# ESP8266.net
KiCad netlist of a schematic drawn in EAGLE
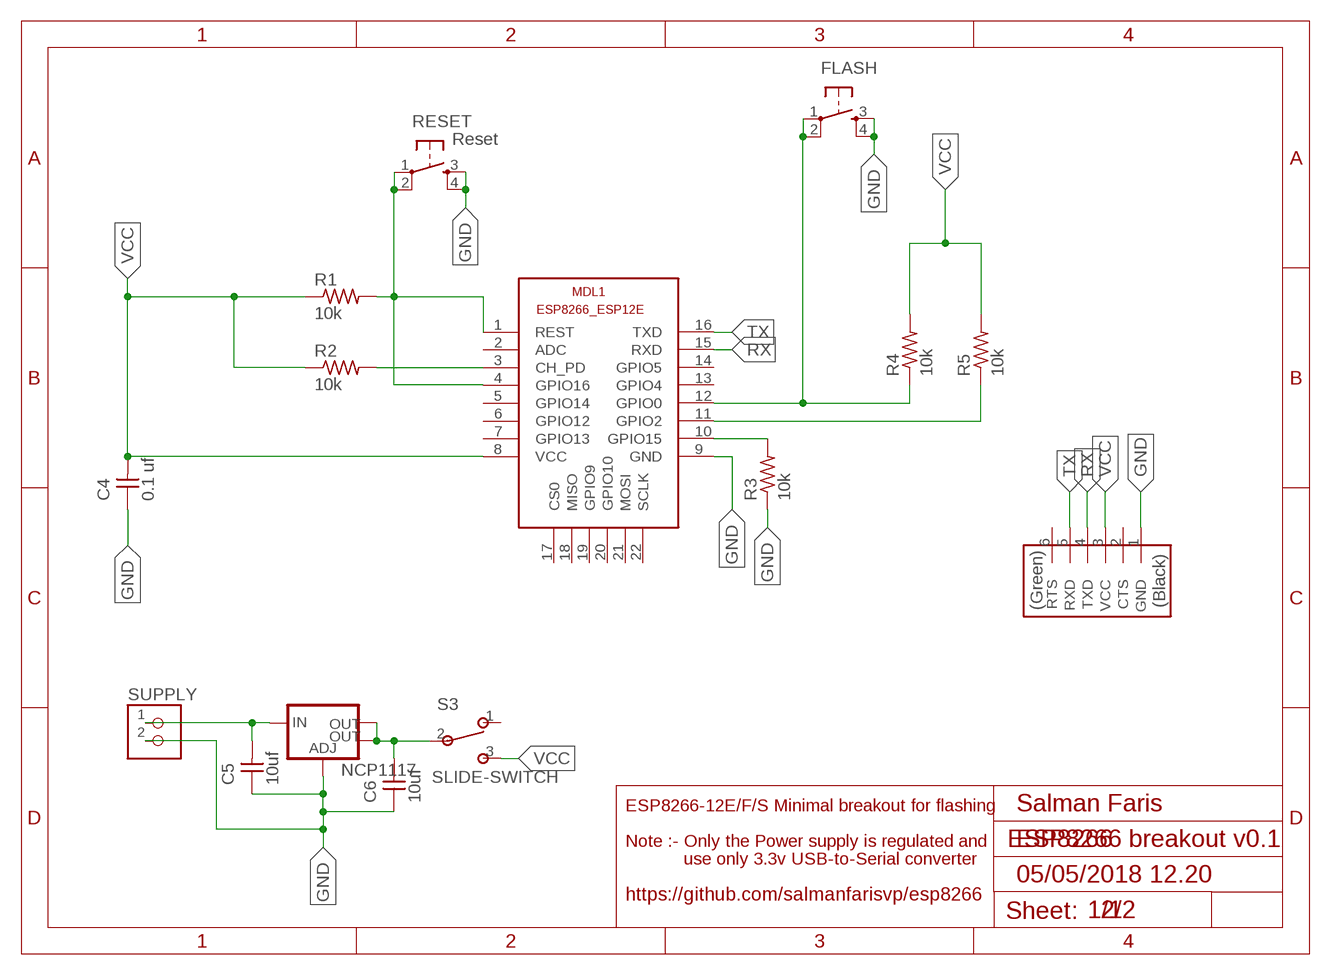
[diagram p0: schematic, sheet 2]

(export (version "E")
  (design (tool "Eeschema 10.0.6"))
  (components
    (comp (ref "C4")
      (value "0.1 uf")
      (footprint "eagle-import:C1206FAB")
      (libsource (lib "eagle-import") (part "CAP-UNPOLARIZEDFAB"))
    )
    (comp (ref "C5")
      (value "10uf")
      (footprint "eagle-import:C1206FAB")
      (libsource (lib "eagle-import") (part "CAP-UNPOLARIZEDFAB"))
    )
    (comp (ref "C6")
      (value "10uf")
      (footprint "eagle-import:C1206FAB")
      (libsource (lib "eagle-import") (part "CAP-UNPOLARIZEDFAB"))
    )
    (comp (ref "FLASH")
      (value "6MM_SWITCH6MM_SWITCH")
      (footprint "eagle-import:6MM_SWITCH")
      (libsource (lib "eagle-import") (part "6MM_SWITCH6MM_SWITCH"))
    )
    (comp (ref "FTDI")
      (value "FTDI-SMD-HEADER")
      (footprint "eagle-import:1X06SMD")
      (libsource (lib "eagle-import") (part "FTDI-SMD-HEADER"))
    )
    (comp (ref "MDL1")
      (value "ESP8266-12EESP8266-ESP12E")
      (footprint "eagle-import:ESP8266-ESP12E")
      (libsource (lib "eagle-import") (part "ESP8266-12EESP8266-ESP12E"))
    )
    (comp (ref "NCP1117")
      (value "V_REG_LM1117SOT223")
      (footprint "eagle-import:SOT223")
      (libsource (lib "eagle-import") (part "V_REG_LM1117SOT223"))
    )
    (comp (ref "R1")
      (value "10k")
      (footprint "eagle-import:R1206FAB")
      (libsource (lib "eagle-import") (part "RES-US1206FAB"))
    )
    (comp (ref "R2")
      (value "10k")
      (footprint "eagle-import:R1206FAB")
      (libsource (lib "eagle-import") (part "RES-US1206FAB"))
    )
    (comp (ref "R3")
      (value "10k")
      (footprint "eagle-import:R1206FAB")
      (libsource (lib "eagle-import") (part "RES-US1206FAB"))
    )
    (comp (ref "R4")
      (value "10k")
      (footprint "eagle-import:R1206FAB")
      (libsource (lib "eagle-import") (part "RES-US1206FAB"))
    )
    (comp (ref "R5")
      (value "10k")
      (footprint "eagle-import:R1206FAB")
      (libsource (lib "eagle-import") (part "RES-US1206FAB"))
    )
    (comp (ref "RESET")
      (value "Reset")
      (footprint "eagle-import:6MM_SWITCH")
      (libsource (lib "eagle-import") (part "6MM_SWITCH6MM_SWITCH"))
    )
    (comp (ref "S3")
      (value "SLIDE-SWITCH")
      (footprint "eagle-import:AYZ0102AGRLC")
      (libsource (lib "eagle-import") (part "SLIDE-SWITCH"))
    )
    (comp (ref "SUPPLY")
      (value "TERM-1X02-FABLAB")
      (footprint "eagle-import:ED555DS-2DS")
      (libsource (lib "eagle-import") (part "TERM-1X02-FABLAB"))
    )
  )
  (nets
    (net (code "1") (name "GND") (class "Default")
      (node (ref "C4") (pin "1") (pinfunction "1_1") (pintype "passive"))
      (node (ref "C5") (pin "1") (pinfunction "1_1") (pintype "passive"))
      (node (ref "C6") (pin "1") (pinfunction "1_1") (pintype "passive"))
      (node (ref "FLASH") (pin "3") (pinfunction "S_3") (pintype "passive"))
      (node (ref "FLASH") (pin "4") (pinfunction "S1_4") (pintype "passive"))
      (node (ref "FTDI") (pin "1") (pinfunction "GND_1") (pintype "bidirectional"))
      (node (ref "MDL1") (pin "9") (pinfunction "GND_9") (pintype "bidirectional"))
      (node (ref "NCP1117") (pin "1") (pinfunction "ADJ_1") (pintype "input"))
      (node (ref "R3") (pin "1") (pinfunction "1_1") (pintype "passive"))
      (node (ref "RESET") (pin "3") (pinfunction "S_3") (pintype "passive"))
      (node (ref "RESET") (pin "4") (pinfunction "S1_4") (pintype "passive"))
      (node (ref "SUPPLY") (pin "2") (pinfunction "2_2") (pintype "passive"))
    )
    (net (code "2") (name "Net-(C6-Pad2)") (class "Default")
      (node (ref "C6") (pin "2") (pinfunction "2_2") (pintype "passive"))
      (node (ref "NCP1117") (pin "2") (pinfunction "OUT_2") (pintype "output"))
      (node (ref "NCP1117") (pin "4") (pinfunction "OUT_4") (pintype "output"))
      (node (ref "S3") (pin "2") (pinfunction "2_2") (pintype "bidirectional"))
    )
    (net (code "3") (name "Net-(FLASH-P)") (class "Default")
      (node (ref "FLASH") (pin "1") (pinfunction "P_1") (pintype "passive"))
      (node (ref "FLASH") (pin "2") (pinfunction "P1_2") (pintype "passive"))
      (node (ref "MDL1") (pin "12") (pinfunction "GPIO0_12") (pintype "bidirectional"))
      (node (ref "R4") (pin "1") (pinfunction "1_1") (pintype "passive"))
    )
    (net (code "4") (name "Net-(MDL1-CH_PD)") (class "Default")
      (node (ref "MDL1") (pin "3") (pinfunction "CH_PD_3") (pintype "bidirectional"))
      (node (ref "R2") (pin "2") (pinfunction "2_2") (pintype "passive"))
    )
    (net (code "5") (name "Net-(MDL1-GPIO2)") (class "Default")
      (node (ref "MDL1") (pin "11") (pinfunction "GPIO2_11") (pintype "bidirectional"))
      (node (ref "R5") (pin "1") (pinfunction "1_1") (pintype "passive"))
    )
    (net (code "6") (name "Net-(MDL1-GPIO15)") (class "Default")
      (node (ref "MDL1") (pin "10") (pinfunction "GPIO15_10") (pintype "bidirectional"))
      (node (ref "R3") (pin "2") (pinfunction "2_2") (pintype "passive"))
    )
    (net (code "7") (name "Net-(MDL1-GPIO16)") (class "Default")
      (node (ref "MDL1") (pin "1") (pinfunction "REST_1") (pintype "bidirectional"))
      (node (ref "MDL1") (pin "4") (pinfunction "GPIO16_4") (pintype "bidirectional"))
      (node (ref "R1") (pin "2") (pinfunction "2_2") (pintype "passive"))
      (node (ref "RESET") (pin "1") (pinfunction "P_1") (pintype "passive"))
      (node (ref "RESET") (pin "2") (pinfunction "P1_2") (pintype "passive"))
    )
    (net (code "8") (name "Net-(NCP1117-IN)") (class "Default")
      (node (ref "C5") (pin "2") (pinfunction "2_2") (pintype "passive"))
      (node (ref "NCP1117") (pin "3") (pinfunction "IN_3") (pintype "input"))
      (node (ref "SUPPLY") (pin "1") (pinfunction "1_1") (pintype "passive"))
    )
    (net (code "9") (name "RX") (class "Default")
      (node (ref "FTDI") (pin "4") (pinfunction "TXD_4") (pintype "bidirectional"))
      (node (ref "MDL1") (pin "15") (pinfunction "RXD_15") (pintype "bidirectional"))
    )
    (net (code "10") (name "TX") (class "Default")
      (node (ref "FTDI") (pin "5") (pinfunction "RXD_5") (pintype "bidirectional"))
      (node (ref "MDL1") (pin "16") (pinfunction "TXD_16") (pintype "bidirectional"))
    )
    (net (code "11") (name "VCC") (class "Default")
      (node (ref "C4") (pin "2") (pinfunction "2_2") (pintype "passive"))
      (node (ref "FTDI") (pin "3") (pinfunction "VCC_3") (pintype "bidirectional"))
      (node (ref "MDL1") (pin "8") (pinfunction "VCC_8") (pintype "bidirectional"))
      (node (ref "R1") (pin "1") (pinfunction "1_1") (pintype "passive"))
      (node (ref "R2") (pin "1") (pinfunction "1_1") (pintype "passive"))
      (node (ref "R4") (pin "2") (pinfunction "2_2") (pintype "passive"))
      (node (ref "R5") (pin "2") (pinfunction "2_2") (pintype "passive"))
      (node (ref "S3") (pin "3") (pinfunction "3_3") (pintype "bidirectional"))
    )
    (net (code "12") (name "unconnected-(FTDI-CTS-Pad2)") (class "Default")
      (node (ref "FTDI") (pin "2") (pinfunction "CTS_2") (pintype "bidirectional"))
    )
    (net (code "13") (name "unconnected-(FTDI-RTS-Pad6)") (class "Default")
      (node (ref "FTDI") (pin "6") (pinfunction "RTS_6") (pintype "bidirectional"))
    )
    (net (code "14") (name "unconnected-(MDL1-ADC-Pad2)") (class "Default")
      (node (ref "MDL1") (pin "2") (pinfunction "ADC_2") (pintype "bidirectional"))
    )
    (net (code "15") (name "unconnected-(MDL1-CS0-Pad17)") (class "Default")
      (node (ref "MDL1") (pin "17") (pinfunction "CS0_17") (pintype "bidirectional"))
    )
    (net (code "16") (name "unconnected-(MDL1-GPIO4-Pad13)") (class "Default")
      (node (ref "MDL1") (pin "13") (pinfunction "GPIO4_13") (pintype "bidirectional"))
    )
    (net (code "17") (name "unconnected-(MDL1-GPIO5-Pad14)") (class "Default")
      (node (ref "MDL1") (pin "14") (pinfunction "GPIO5_14") (pintype "bidirectional"))
    )
    (net (code "18") (name "unconnected-(MDL1-GPIO9-Pad19)") (class "Default")
      (node (ref "MDL1") (pin "19") (pinfunction "GPIO9_19") (pintype "bidirectional"))
    )
    (net (code "19") (name "unconnected-(MDL1-GPIO10-Pad20)") (class "Default")
      (node (ref "MDL1") (pin "20") (pinfunction "GPIO10_20") (pintype "bidirectional"))
    )
    (net (code "20") (name "unconnected-(MDL1-GPIO12-Pad6)") (class "Default")
      (node (ref "MDL1") (pin "6") (pinfunction "GPIO12_6") (pintype "bidirectional"))
    )
    (net (code "21") (name "unconnected-(MDL1-GPIO13-Pad7)") (class "Default")
      (node (ref "MDL1") (pin "7") (pinfunction "GPIO13_7") (pintype "bidirectional"))
    )
    (net (code "22") (name "unconnected-(MDL1-GPIO14-Pad5)") (class "Default")
      (node (ref "MDL1") (pin "5") (pinfunction "GPIO14_5") (pintype "bidirectional"))
    )
    (net (code "23") (name "unconnected-(MDL1-MISO-Pad18)") (class "Default")
      (node (ref "MDL1") (pin "18") (pinfunction "MISO_18") (pintype "bidirectional"))
    )
    (net (code "24") (name "unconnected-(MDL1-MOSI-Pad21)") (class "Default")
      (node (ref "MDL1") (pin "21") (pinfunction "MOSI_21") (pintype "bidirectional"))
    )
    (net (code "25") (name "unconnected-(MDL1-SCLK-Pad22)") (class "Default")
      (node (ref "MDL1") (pin "22") (pinfunction "SCLK_22") (pintype "bidirectional"))
    )
    (net (code "26") (name "unconnected-(S3-Pad1)") (class "Default")
      (node (ref "S3") (pin "1") (pinfunction "1_1") (pintype "bidirectional"))
    )
  )
)
